# passive_RC_low_pass_filter.net
KiCad netlist of a schematic drawn in EAGLE
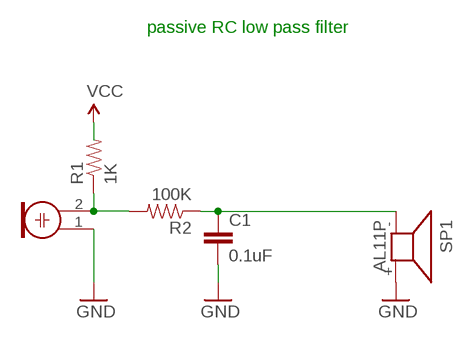
[diagram p0: schematic, sheet 1]

(export (version "E")
  (design (tool "Eeschema 10.0.6"))
  (components
    (comp (ref "C1")
      (value "0.1uF")
      (footprint "eagle-import:CAP-PTH-SMALL2")
      (libsource (lib "eagle-import") (part "CAPPTH2"))
    )
    (comp (ref "M1")
      (value "ELECTRET_MICROPHON-F6050AP")
      (footprint "eagle-import:F6050AP")
      (libsource (lib "eagle-import") (part "ELECTRET_MICROPHON-F6050AP"))
    )
    (comp (ref "R1")
      (value "1K")
      (footprint "eagle-import:AXIAL-0.3")
      (libsource (lib "eagle-import") (part "RESISTORAXIAL-0.3"))
    )
    (comp (ref "R2")
      (value "100K")
      (footprint "eagle-import:AXIAL-0.3")
      (libsource (lib "eagle-import") (part "RESISTORAXIAL-0.3"))
    )
    (comp (ref "SP1")
      (value "AL11P")
      (footprint "eagle-import:AL11P")
      (libsource (lib "eagle-import") (part "AL11P"))
    )
  )
  (nets
    (net (code "1") (name "GND") (class "Default")
      (node (ref "C1") (pin "2") (pinfunction "2_2") (pintype "passive"))
      (node (ref "M1") (pin "1") (pinfunction "1_1") (pintype "passive"))
      (node (ref "SP1") (pin "+") (pinfunction "2_+") (pintype "passive"))
    )
    (net (code "2") (name "Net-(R1-1)") (class "Default")
      (node (ref "M1") (pin "2") (pinfunction "2_2") (pintype "passive"))
      (node (ref "R1") (pin "P$1") (pinfunction "1_P$1") (pintype "passive"))
      (node (ref "R2") (pin "P$2") (pinfunction "2_P$2") (pintype "passive"))
    )
    (net (code "3") (name "Net-(R2-1)") (class "Default")
      (node (ref "C1") (pin "1") (pinfunction "1_1") (pintype "passive"))
      (node (ref "R2") (pin "P$1") (pinfunction "1_P$1") (pintype "passive"))
      (node (ref "SP1") (pin "-") (pinfunction "1_-") (pintype "passive"))
    )
    (net (code "4") (name "VCC") (class "Default")
      (node (ref "R1") (pin "P$2") (pinfunction "2_P$2") (pintype "passive"))
    )
  )
)
